# FPGA_I_J.net
KiCad netlist of a schematic drawn in Altium Designer
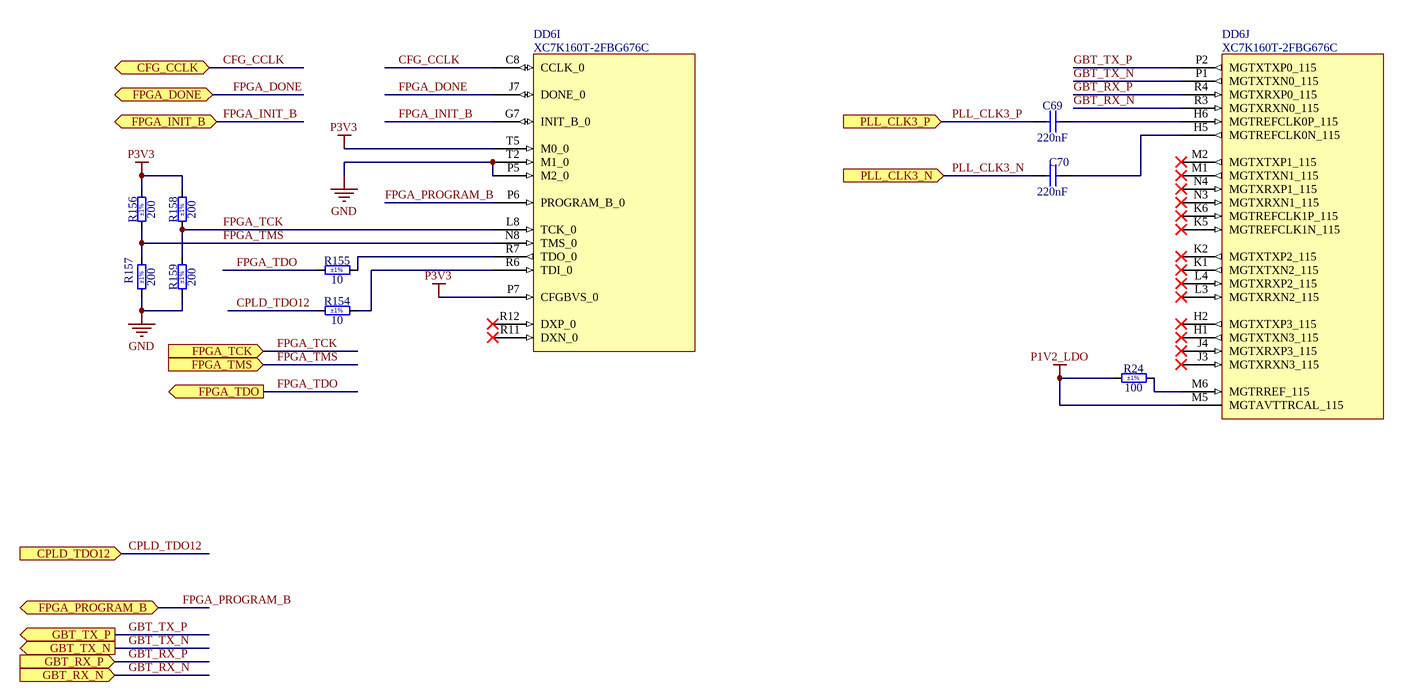
[diagram p0: FPGA_I_J.SchDoc]

(export (version "E")
  (design (tool "Eeschema 10.0.6"))
  (components
    (comp (ref "C69")
      (value "220nF")
      (footprint "CAPC1608X87N")
      (description "Non-polarised capacitor")
      (fields
        (field (name "PART NUMBER") "CC0603_220NF_25V_10%_X7R")
        (field (name "VOLTAGE") "25V")
        (field (name "AUTHOR") "CERN DEM JLC")
      )
      (libsource (lib "Capacitors") (part "Capacitor - non polarized"))
    )
    (comp (ref "C70")
      (value "220nF")
      (footprint "CAPC1608X87N")
      (description "Non-polarised capacitor")
      (fields
        (field (name "PART NUMBER") "CC0603_220NF_25V_10%_X7R")
        (field (name "VOLTAGE") "25V")
        (field (name "AUTHOR") "CERN DEM JLC")
      )
      (libsource (lib "Capacitors") (part "Capacitor - non polarized"))
    )
    (comp (ref "DD6")
      (value "XC7K160T-2FBG676C")
      (footprint "BGA676C100P26X26_2700X2700X254")
      (description "KINTEX-7, FPGA, 676-Ball BGA, Pb-Free")
      (fields (field (name "MANUFACTURER") "XILINX") (field (name "AUTHOR") "CERN DEM BC"))
      (libsource (lib "ICs And Semiconductors") (part "XC7K160T-xFBG676"))
    )
    (comp (ref "R24")
      (value "100")
      (footprint "RESC1608X55N")
      (description "Resistor - 1%")
      (fields
        (field (name "TOLERANCE") "±1%")
        (field (name "PART NUMBER") "R0603_100R_1%_0.1W_100PPM")
        (field (name "POWER") "0.1W")
        (field (name "AUTHOR") "CERN DEM JLC")
      )
      (libsource (lib "Resistors") (part "Resistor - 1%"))
    )
    (comp (ref "R154")
      (value "10")
      (footprint "RESC2012X70N")
      (description "Resistor - 1%")
      (fields
        (field (name "TOLERANCE") "±1%")
        (field (name "PART NUMBER") "R0805_10R_1%_0.125W_100PPM_PANASONIC_ERJ")
        (field (name "POWER") "0.125W")
        (field (name "AUTHOR") "CERN DEM HF")
      )
      (libsource (lib "Resistors") (part "Resistor - 1%"))
    )
    (comp (ref "R155")
      (value "10")
      (footprint "RESC2012X70N")
      (description "Resistor - 1%")
      (fields
        (field (name "TOLERANCE") "±1%")
        (field (name "PART NUMBER") "R0805_10R_1%_0.125W_100PPM_PANASONIC_ERJ")
        (field (name "POWER") "0.125W")
        (field (name "AUTHOR") "CERN DEM HF")
      )
      (libsource (lib "Resistors") (part "Resistor - 1%"))
    )
    (comp (ref "R156")
      (value "200")
      (footprint "RESC2012X60N")
      (description "Resistor - 1%")
      (fields
        (field (name "TOLERANCE") "±1%")
        (field (name "PART NUMBER") "R0805_200R_1%_0.125W_100PPM")
        (field (name "POWER") "0.125W")
        (field (name "AUTHOR") "CERN DEM JLC")
      )
      (libsource (lib "Resistors") (part "Resistor - 1%"))
    )
    (comp (ref "R157")
      (value "200")
      (footprint "RESC2012X60N")
      (description "Resistor - 1%")
      (fields
        (field (name "TOLERANCE") "±1%")
        (field (name "PART NUMBER") "R0805_200R_1%_0.125W_100PPM")
        (field (name "POWER") "0.125W")
        (field (name "AUTHOR") "CERN DEM JLC")
      )
      (libsource (lib "Resistors") (part "Resistor - 1%"))
    )
    (comp (ref "R158")
      (value "200")
      (footprint "RESC2012X60N")
      (description "Resistor - 1%")
      (fields
        (field (name "TOLERANCE") "±1%")
        (field (name "PART NUMBER") "R0805_200R_1%_0.125W_100PPM")
        (field (name "POWER") "0.125W")
        (field (name "AUTHOR") "CERN DEM JLC")
      )
      (libsource (lib "Resistors") (part "Resistor - 1%"))
    )
    (comp (ref "R159")
      (value "200")
      (footprint "RESC2012X60N")
      (description "Resistor - 1%")
      (fields
        (field (name "TOLERANCE") "±1%")
        (field (name "PART NUMBER") "R0805_200R_1%_0.125W_100PPM")
        (field (name "POWER") "0.125W")
        (field (name "AUTHOR") "CERN DEM JLC")
      )
      (libsource (lib "Resistors") (part "Resistor - 1%"))
    )
  )
  (nets
    (net (code "1") (name "/CFG_CCLK") (class "Default")
      (node (ref "DD6") (pin "C8") (pinfunction "CCLK_0_C8") (pintype "bidirectional"))
    )
    (net (code "2") (name "/CPLD_TDO12") (class "Default")
      (node (ref "R154") (pin "1") (pinfunction "1_1") (pintype "passive"))
    )
    (net (code "3") (name "/FPGA_DONE") (class "Default")
      (node (ref "DD6") (pin "J7") (pinfunction "DONE_0_J7") (pintype "bidirectional"))
    )
    (net (code "4") (name "/FPGA_INIT_B") (class "Default")
      (node (ref "DD6") (pin "G7") (pinfunction "INIT_B_0_G7") (pintype "bidirectional"))
    )
    (net (code "5") (name "/FPGA_PROGRAM_B") (class "Default")
      (node (ref "DD6") (pin "P6") (pinfunction "PROGRAM_B_0_P6") (pintype "input"))
    )
    (net (code "6") (name "/FPGA_TCK") (class "Default")
      (node (ref "DD6") (pin "L8") (pinfunction "TCK_0_L8") (pintype "input"))
      (node (ref "R158") (pin "1") (pinfunction "1_1") (pintype "passive"))
      (node (ref "R159") (pin "2") (pinfunction "2_2") (pintype "passive"))
    )
    (net (code "7") (name "/FPGA_TDO") (class "Default")
      (node (ref "R155") (pin "1") (pinfunction "1_1") (pintype "passive"))
    )
    (net (code "8") (name "/FPGA_TMS") (class "Default")
      (node (ref "DD6") (pin "N8") (pinfunction "TMS_0_N8") (pintype "input"))
      (node (ref "R156") (pin "1") (pinfunction "1_1") (pintype "passive"))
      (node (ref "R157") (pin "2") (pinfunction "2_2") (pintype "passive"))
    )
    (net (code "9") (name "/GBT_RX_N") (class "Default")
      (node (ref "DD6") (pin "R3") (pinfunction "MGTXRXN0_115_R3") (pintype "input"))
    )
    (net (code "10") (name "/GBT_RX_P") (class "Default")
      (node (ref "DD6") (pin "R4") (pinfunction "MGTXRXP0_115_R4") (pintype "input"))
    )
    (net (code "11") (name "/GBT_TX_N") (class "Default")
      (node (ref "DD6") (pin "P1") (pinfunction "MGTXTXN0_115_P1") (pintype "output"))
    )
    (net (code "12") (name "/GBT_TX_P") (class "Default")
      (node (ref "DD6") (pin "P2") (pinfunction "MGTXTXP0_115_P2") (pintype "output"))
    )
    (net (code "13") (name "/PLL_CLK3_N") (class "Default")
      (node (ref "C70") (pin "1") (pinfunction "1_1") (pintype "passive"))
    )
    (net (code "14") (name "/PLL_CLK3_P") (class "Default")
      (node (ref "C69") (pin "1") (pinfunction "1_1") (pintype "passive"))
    )
    (net (code "15") (name "GND") (class "Default")
      (node (ref "DD6") (pin "P5") (pinfunction "M2_0_P5") (pintype "input"))
      (node (ref "DD6") (pin "T2") (pinfunction "M1_0_T2") (pintype "input"))
      (node (ref "R157") (pin "1") (pinfunction "1_1") (pintype "passive"))
      (node (ref "R159") (pin "1") (pinfunction "1_1") (pintype "passive"))
    )
    (net (code "16") (name "Net-(DD6I-TDI_0)") (class "Default")
      (node (ref "DD6") (pin "R6") (pinfunction "TDI_0_R6") (pintype "input"))
      (node (ref "R154") (pin "2") (pinfunction "2_2") (pintype "passive"))
    )
    (net (code "17") (name "Net-(DD6I-TDO_0)") (class "Default")
      (node (ref "DD6") (pin "R7") (pinfunction "TDO_0_R7") (pintype "output"))
      (node (ref "R155") (pin "2") (pinfunction "2_2") (pintype "passive"))
    )
    (net (code "18") (name "Net-(DD6J-MGTREFCLK0N_115)") (class "Default")
      (node (ref "C70") (pin "2") (pinfunction "2_2") (pintype "passive"))
      (node (ref "DD6") (pin "H5") (pinfunction "MGTREFCLK0N_115_H5") (pintype "output"))
    )
    (net (code "19") (name "Net-(DD6J-MGTREFCLK0P_115)") (class "Default")
      (node (ref "C69") (pin "2") (pinfunction "2_2") (pintype "passive"))
      (node (ref "DD6") (pin "H6") (pinfunction "MGTREFCLK0P_115_H6") (pintype "input"))
    )
    (net (code "20") (name "Net-(DD6J-MGTRREF_115)") (class "Default")
      (node (ref "DD6") (pin "M6") (pinfunction "MGTRREF_115_M6") (pintype "input"))
      (node (ref "R24") (pin "2") (pinfunction "2_2") (pintype "passive"))
    )
    (net (code "21") (name "P1V2_LDO") (class "Default")
      (node (ref "DD6") (pin "M5") (pinfunction "MGTAVTTRCAL_115_M5") (pintype "passive"))
      (node (ref "R24") (pin "1") (pinfunction "1_1") (pintype "passive"))
    )
    (net (code "22") (name "P3V3") (class "Default")
      (node (ref "DD6") (pin "P7") (pinfunction "CFGBVS_0_P7") (pintype "input"))
      (node (ref "DD6") (pin "T5") (pinfunction "M0_0_T5") (pintype "input"))
      (node (ref "R156") (pin "2") (pinfunction "2_2") (pintype "passive"))
      (node (ref "R158") (pin "2") (pinfunction "2_2") (pintype "passive"))
    )
    (net (code "23") (name "unconnected-(DD6I-DXN_0-PadR11)") (class "Default")
      (node (ref "DD6") (pin "R11") (pinfunction "DXN_0_R11") (pintype "input+no_connect"))
    )
    (net (code "24") (name "unconnected-(DD6I-DXP_0-PadR12)") (class "Default")
      (node (ref "DD6") (pin "R12") (pinfunction "DXP_0_R12") (pintype "input+no_connect"))
    )
    (net (code "25") (name "unconnected-(DD6J-MGTREFCLK1N_115-PadK5)") (class "Default")
      (node (ref "DD6") (pin "K5") (pinfunction "MGTREFCLK1N_115_K5") (pintype "input+no_connect"))
    )
    (net (code "26") (name "unconnected-(DD6J-MGTREFCLK1P_115-PadK6)") (class "Default")
      (node (ref "DD6") (pin "K6") (pinfunction "MGTREFCLK1P_115_K6") (pintype "input+no_connect"))
    )
    (net (code "27") (name "unconnected-(DD6J-MGTXRXN1_115-PadN3)") (class "Default")
      (node (ref "DD6") (pin "N3") (pinfunction "MGTXRXN1_115_N3") (pintype "input+no_connect"))
    )
    (net (code "28") (name "unconnected-(DD6J-MGTXRXN2_115-PadL3)") (class "Default")
      (node (ref "DD6") (pin "L3") (pinfunction "MGTXRXN2_115_L3") (pintype "input+no_connect"))
    )
    (net (code "29") (name "unconnected-(DD6J-MGTXRXN3_115-PadJ3)") (class "Default")
      (node (ref "DD6") (pin "J3") (pinfunction "MGTXRXN3_115_J3") (pintype "input+no_connect"))
    )
    (net (code "30") (name "unconnected-(DD6J-MGTXRXP1_115-PadN4)") (class "Default")
      (node (ref "DD6") (pin "N4") (pinfunction "MGTXRXP1_115_N4") (pintype "input+no_connect"))
    )
    (net (code "31") (name "unconnected-(DD6J-MGTXRXP2_115-PadL4)") (class "Default")
      (node (ref "DD6") (pin "L4") (pinfunction "MGTXRXP2_115_L4") (pintype "input+no_connect"))
    )
    (net (code "32") (name "unconnected-(DD6J-MGTXRXP3_115-PadJ4)") (class "Default")
      (node (ref "DD6") (pin "J4") (pinfunction "MGTXRXP3_115_J4") (pintype "input+no_connect"))
    )
    (net (code "33") (name "unconnected-(DD6J-MGTXTXN1_115-PadM1)") (class "Default")
      (node (ref "DD6") (pin "M1") (pinfunction "MGTXTXN1_115_M1") (pintype "output+no_connect"))
    )
    (net (code "34") (name "unconnected-(DD6J-MGTXTXN2_115-PadK1)") (class "Default")
      (node (ref "DD6") (pin "K1") (pinfunction "MGTXTXN2_115_K1") (pintype "output+no_connect"))
    )
    (net (code "35") (name "unconnected-(DD6J-MGTXTXN3_115-PadH1)") (class "Default")
      (node (ref "DD6") (pin "H1") (pinfunction "MGTXTXN3_115_H1") (pintype "output+no_connect"))
    )
    (net (code "36") (name "unconnected-(DD6J-MGTXTXP1_115-PadM2)") (class "Default")
      (node (ref "DD6") (pin "M2") (pinfunction "MGTXTXP1_115_M2") (pintype "output+no_connect"))
    )
    (net (code "37") (name "unconnected-(DD6J-MGTXTXP2_115-PadK2)") (class "Default")
      (node (ref "DD6") (pin "K2") (pinfunction "MGTXTXP2_115_K2") (pintype "output+no_connect"))
    )
    (net (code "38") (name "unconnected-(DD6J-MGTXTXP3_115-PadH2)") (class "Default")
      (node (ref "DD6") (pin "H2") (pinfunction "MGTXTXP3_115_H2") (pintype "output+no_connect"))
    )
  )
)
